# testbench.net
KiCad netlist of a schematic drawn in EAGLE
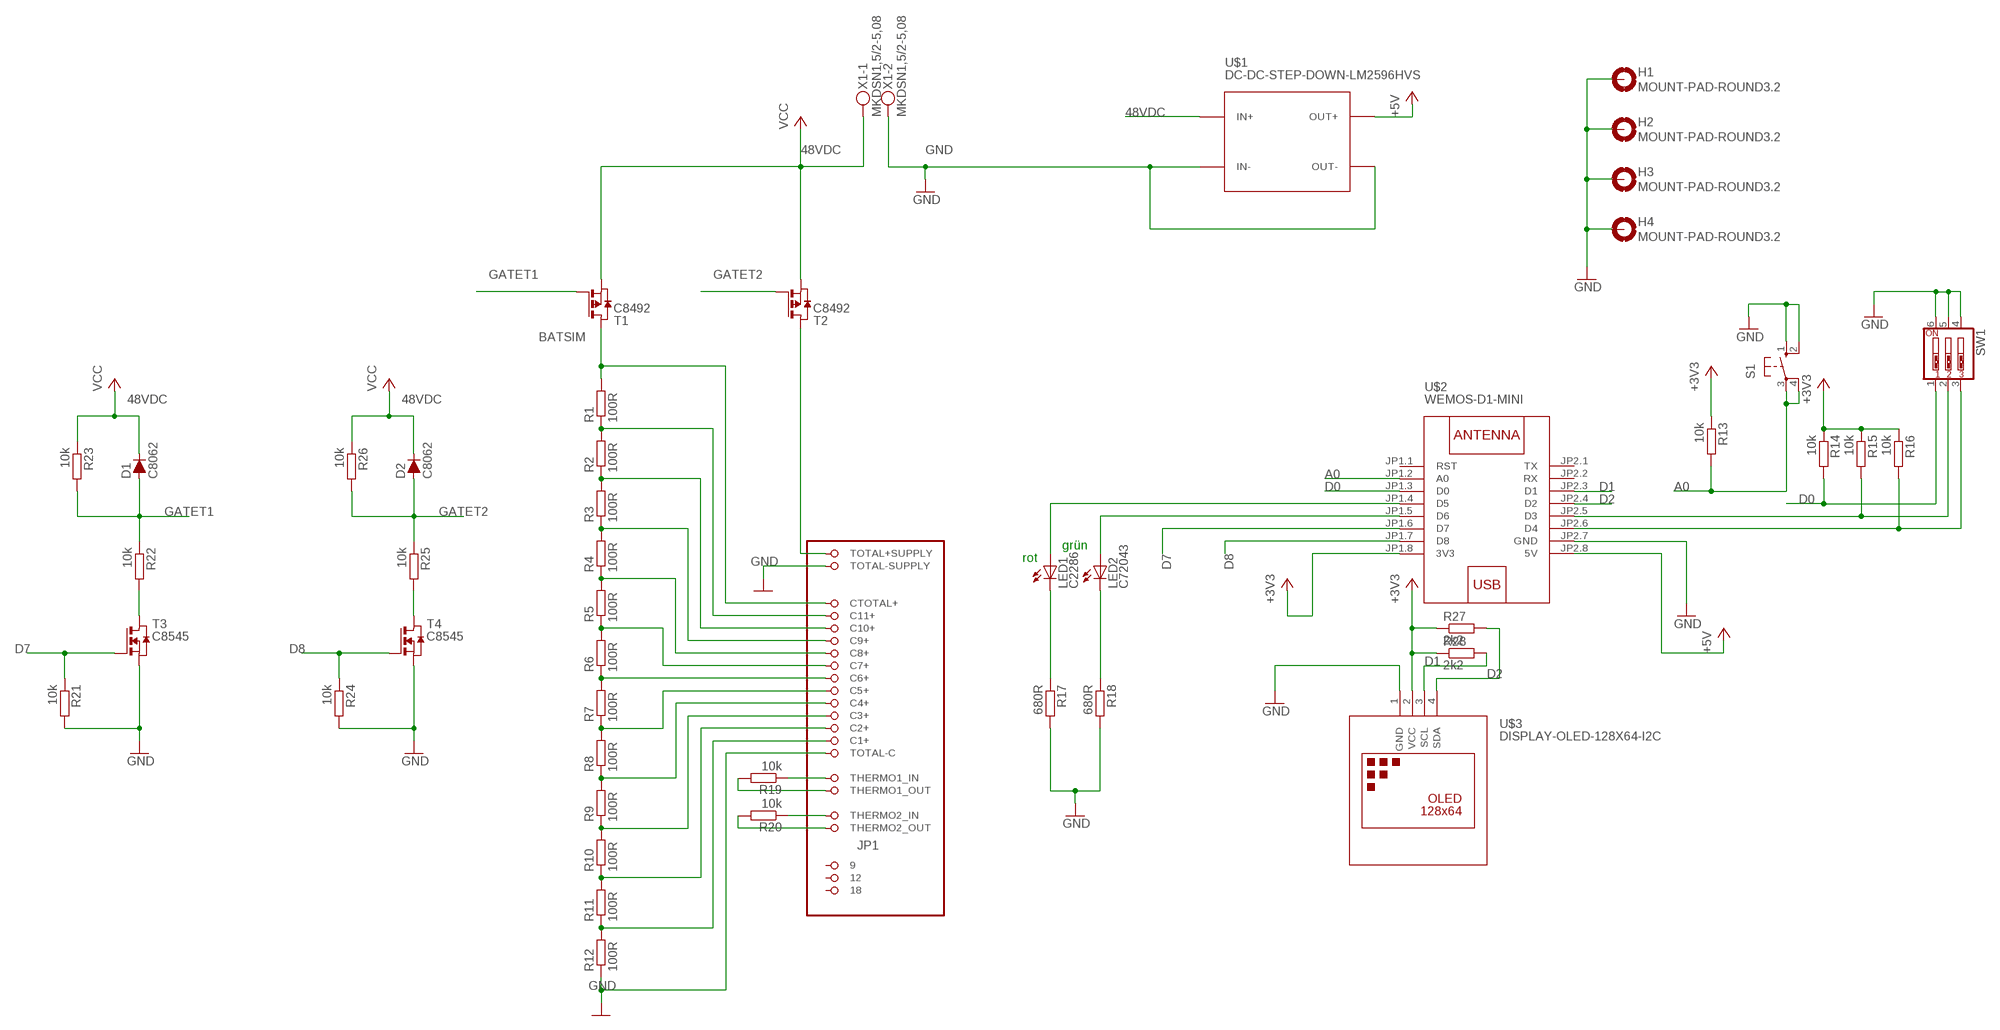
[diagram p0: schematic, sheet 1]

(export (version "E")
  (design (tool "Eeschema 10.0.6"))
  (components
    (comp (ref "D1")
      (value "C8062")
      (footprint "eagle-import:MELF-MLL34")
      (libsource (lib "eagle-import") (part "D-FILL-MLL-34"))
    )
    (comp (ref "D2")
      (value "C8062")
      (footprint "eagle-import:MELF-MLL34")
      (libsource (lib "eagle-import") (part "D-FILL-MLL-34"))
    )
    (comp (ref "H1")
      (value "MOUNT-PAD-ROUND3.2")
      (footprint "eagle-import:3,2-PAD")
      (libsource (lib "eagle-import") (part "MOUNT-PAD-ROUND3.2"))
    )
    (comp (ref "H2")
      (value "MOUNT-PAD-ROUND3.2")
      (footprint "eagle-import:3,2-PAD")
      (libsource (lib "eagle-import") (part "MOUNT-PAD-ROUND3.2"))
    )
    (comp (ref "H3")
      (value "MOUNT-PAD-ROUND3.2")
      (footprint "eagle-import:3,2-PAD")
      (libsource (lib "eagle-import") (part "MOUNT-PAD-ROUND3.2"))
    )
    (comp (ref "H4")
      (value "MOUNT-PAD-ROUND3.2")
      (footprint "eagle-import:3,2-PAD")
      (libsource (lib "eagle-import") (part "MOUNT-PAD-ROUND3.2"))
    )
    (comp (ref "JP1")
      (value "PINHD-2X11_MEB12S_MODULSEITE_SMD")
      (footprint "eagle-import:2X11_MEB12S_MODULSEITE_SMD")
      (libsource (lib "eagle-import") (part "PINHD-2X11_MEB12S_MODULSEITE_SMD"))
    )
    (comp (ref "LED1")
      (value "C2286")
      (footprint "eagle-import:CHIP-LED0603")
      (libsource (lib "eagle-import") (part "LEDCHIP-LED0603"))
    )
    (comp (ref "LED2")
      (value "C72043")
      (footprint "eagle-import:CHIP-LED0603")
      (libsource (lib "eagle-import") (part "LEDCHIP-LED0603"))
    )
    (comp (ref "R1")
      (value "100R")
      (footprint "eagle-import:R0805")
      (libsource (lib "eagle-import") (part "R-EU_R0805"))
    )
    (comp (ref "R2")
      (value "100R")
      (footprint "eagle-import:R0805")
      (libsource (lib "eagle-import") (part "R-EU_R0805"))
    )
    (comp (ref "R3")
      (value "100R")
      (footprint "eagle-import:R0805")
      (libsource (lib "eagle-import") (part "R-EU_R0805"))
    )
    (comp (ref "R4")
      (value "100R")
      (footprint "eagle-import:R0805")
      (libsource (lib "eagle-import") (part "R-EU_R0805"))
    )
    (comp (ref "R5")
      (value "100R")
      (footprint "eagle-import:R0805")
      (libsource (lib "eagle-import") (part "R-EU_R0805"))
    )
    (comp (ref "R6")
      (value "100R")
      (footprint "eagle-import:R0805")
      (libsource (lib "eagle-import") (part "R-EU_R0805"))
    )
    (comp (ref "R7")
      (value "100R")
      (footprint "eagle-import:R0805")
      (libsource (lib "eagle-import") (part "R-EU_R0805"))
    )
    (comp (ref "R8")
      (value "100R")
      (footprint "eagle-import:R0805")
      (libsource (lib "eagle-import") (part "R-EU_R0805"))
    )
    (comp (ref "R9")
      (value "100R")
      (footprint "eagle-import:R0805")
      (libsource (lib "eagle-import") (part "R-EU_R0805"))
    )
    (comp (ref "R10")
      (value "100R")
      (footprint "eagle-import:R0805")
      (libsource (lib "eagle-import") (part "R-EU_R0805"))
    )
    (comp (ref "R11")
      (value "100R")
      (footprint "eagle-import:R0805")
      (libsource (lib "eagle-import") (part "R-EU_R0805"))
    )
    (comp (ref "R12")
      (value "100R")
      (footprint "eagle-import:R0805")
      (libsource (lib "eagle-import") (part "R-EU_R0805"))
    )
    (comp (ref "R13")
      (value "10k")
      (footprint "eagle-import:R0805")
      (libsource (lib "eagle-import") (part "R-EU_R0805"))
    )
    (comp (ref "R14")
      (value "10k")
      (footprint "eagle-import:R0805")
      (libsource (lib "eagle-import") (part "R-EU_R0805"))
    )
    (comp (ref "R15")
      (value "10k")
      (footprint "eagle-import:R0805")
      (libsource (lib "eagle-import") (part "R-EU_R0805"))
    )
    (comp (ref "R16")
      (value "10k")
      (footprint "eagle-import:R0805")
      (libsource (lib "eagle-import") (part "R-EU_R0805"))
    )
    (comp (ref "R17")
      (value "680R")
      (footprint "eagle-import:R0805")
      (libsource (lib "eagle-import") (part "R-EU_R0805"))
    )
    (comp (ref "R18")
      (value "680R")
      (footprint "eagle-import:R0805")
      (libsource (lib "eagle-import") (part "R-EU_R0805"))
    )
    (comp (ref "R19")
      (value "10k")
      (footprint "eagle-import:R0805")
      (libsource (lib "eagle-import") (part "R-EU_R0805"))
    )
    (comp (ref "R20")
      (value "10k")
      (footprint "eagle-import:R0805")
      (libsource (lib "eagle-import") (part "R-EU_R0805"))
    )
    (comp (ref "R21")
      (value "10k")
      (footprint "eagle-import:R0805")
      (libsource (lib "eagle-import") (part "R-EU_R0805"))
    )
    (comp (ref "R22")
      (value "10k")
      (footprint "eagle-import:R0805")
      (libsource (lib "eagle-import") (part "R-EU_R0805"))
    )
    (comp (ref "R23")
      (value "10k")
      (footprint "eagle-import:R0805")
      (libsource (lib "eagle-import") (part "R-EU_R0805"))
    )
    (comp (ref "R24")
      (value "10k")
      (footprint "eagle-import:R0805")
      (libsource (lib "eagle-import") (part "R-EU_R0805"))
    )
    (comp (ref "R25")
      (value "10k")
      (footprint "eagle-import:R0805")
      (libsource (lib "eagle-import") (part "R-EU_R0805"))
    )
    (comp (ref "R26")
      (value "10k")
      (footprint "eagle-import:R0805")
      (libsource (lib "eagle-import") (part "R-EU_R0805"))
    )
    (comp (ref "R27")
      (value "2k2")
      (footprint "eagle-import:R0805")
      (libsource (lib "eagle-import") (part "R-EU_R0805"))
    )
    (comp (ref "R28")
      (value "2k2")
      (footprint "eagle-import:R0805")
      (libsource (lib "eagle-import") (part "R-EU_R0805"))
    )
    (comp (ref "S1")
      (value "10-XX")
      (footprint "eagle-import:B3F-10XX")
      (fields (field (name "MPN") "B3F-1000"))
      (libsource (lib "eagle-import") (part "10-XX"))
    )
    (comp (ref "SW1")
      (value "SW_DIP-3")
      (footprint "eagle-import:EDG-03")
      (libsource (lib "eagle-import") (part "SW_DIP-3"))
    )
    (comp (ref "T1")
      (value "C8492")
      (footprint "eagle-import:SOT-23")
      (libsource (lib "eagle-import") (part "PMOSSOT23"))
    )
    (comp (ref "T2")
      (value "C8492")
      (footprint "eagle-import:SOT-23")
      (libsource (lib "eagle-import") (part "PMOSSOT23"))
    )
    (comp (ref "T3")
      (value "C8545")
      (footprint "eagle-import:SOT-23")
      (libsource (lib "eagle-import") (part "NMOSSOT23"))
    )
    (comp (ref "T4")
      (value "C8545")
      (footprint "eagle-import:SOT-23")
      (libsource (lib "eagle-import") (part "NMOSSOT23"))
    )
    (comp (ref "U$1")
      (value "DC-DC-STEP-DOWN-LM2596HVS")
      (footprint "eagle-import:DC-DC-STEP-DOWN-LM2596HVS")
      (libsource (lib "eagle-import") (part "DC-DC-STEP-DOWN-LM2596HVS"))
    )
    (comp (ref "U$2")
      (value "WEMOS-D1-MINI")
      (footprint "eagle-import:WEMOS-D1-MINI")
      (libsource (lib "eagle-import") (part "WEMOS-D1-MINI"))
    )
    (comp (ref "U$3")
      (value "DISPLAY-OLED-128X64-I2C")
      (footprint "eagle-import:DISPLAY-OLED-128X64-I2C")
      (libsource (lib "eagle-import") (part "DISPLAY-OLED-128X64-I2C"))
    )
    (comp (ref "X1")
      (value "MKDSN1,5/2-5,08")
      (footprint "eagle-import:MKDSN1,5_2-5,08")
      (libsource (lib "eagle-import") (part "MKDSN1,5/2-5,08"))
    )
  )
  (nets
    (net (code "1") (name "+3V3") (class "Default")
      (node (ref "R13") (pin "1") (pinfunction "1_1") (pintype "passive"))
      (node (ref "R14") (pin "1") (pinfunction "1_1") (pintype "passive"))
      (node (ref "R15") (pin "1") (pinfunction "1_1") (pintype "passive"))
      (node (ref "R16") (pin "1") (pinfunction "1_1") (pintype "passive"))
      (node (ref "R27") (pin "1") (pinfunction "1_1") (pintype "passive"))
      (node (ref "R28") (pin "1") (pinfunction "1_1") (pintype "passive"))
      (node (ref "U$2") (pin "JP1.8") (pinfunction "3V3_JP1.8") (pintype "power_in"))
      (node (ref "U$3") (pin "2") (pinfunction "VCC_2") (pintype "power_in"))
    )
    (net (code "2") (name "+5V") (class "Default")
      (node (ref "U$1") (pin "OUT+") (pinfunction "OUT+_OUT+") (pintype "bidirectional"))
      (node (ref "U$2") (pin "JP2.8") (pinfunction "5V_JP2.8") (pintype "power_in"))
    )
    (net (code "3") (name "/A0") (class "Default")
      (node (ref "R13") (pin "2") (pinfunction "2_2") (pintype "passive"))
      (node (ref "S1") (pin "3") (pinfunction "P_3") (pintype "passive"))
      (node (ref "S1") (pin "4") (pinfunction "P1_4") (pintype "passive"))
      (node (ref "U$2") (pin "JP1.2") (pinfunction "A0_JP1.2") (pintype "bidirectional"))
    )
    (net (code "4") (name "/BATSIM") (class "Default")
      (node (ref "JP1") (pin "21") (pinfunction "CTOTAL+_21") (pintype "passive"))
      (node (ref "R1") (pin "2") (pinfunction "2_2") (pintype "passive"))
      (node (ref "T1") (pin "1") (pinfunction "D_1") (pintype "passive"))
    )
    (net (code "5") (name "/D0") (class "Default")
      (node (ref "R14") (pin "2") (pinfunction "2_2") (pintype "passive"))
      (node (ref "SW1") (pin "1") (pinfunction "1_1") (pintype "passive"))
      (node (ref "U$2") (pin "JP1.3") (pinfunction "D0_JP1.3") (pintype "bidirectional"))
    )
    (net (code "6") (name "/D1") (class "Default")
      (node (ref "R28") (pin "2") (pinfunction "2_2") (pintype "passive"))
      (node (ref "U$2") (pin "JP2.3") (pinfunction "D1_JP2.3") (pintype "bidirectional"))
      (node (ref "U$3") (pin "3") (pinfunction "SCL_3") (pintype "bidirectional"))
    )
    (net (code "7") (name "/D2") (class "Default")
      (node (ref "R27") (pin "2") (pinfunction "2_2") (pintype "passive"))
      (node (ref "U$2") (pin "JP2.4") (pinfunction "D2_JP2.4") (pintype "bidirectional"))
      (node (ref "U$3") (pin "4") (pinfunction "SDA_4") (pintype "bidirectional"))
    )
    (net (code "8") (name "/D7") (class "Default")
      (node (ref "R21") (pin "1") (pinfunction "1_1") (pintype "passive"))
      (node (ref "T3") (pin "3") (pinfunction "G_3") (pintype "passive"))
      (node (ref "U$2") (pin "JP1.6") (pinfunction "D7_JP1.6") (pintype "bidirectional"))
    )
    (net (code "9") (name "/D8") (class "Default")
      (node (ref "R24") (pin "1") (pinfunction "1_1") (pintype "passive"))
      (node (ref "T4") (pin "3") (pinfunction "G_3") (pintype "passive"))
      (node (ref "U$2") (pin "JP1.7") (pinfunction "D8_JP1.7") (pintype "bidirectional"))
    )
    (net (code "10") (name "/GATET1") (class "Default")
      (node (ref "D1") (pin "2") (pinfunction "A_2") (pintype "passive"))
      (node (ref "R22") (pin "1") (pinfunction "1_1") (pintype "passive"))
      (node (ref "R23") (pin "2") (pinfunction "2_2") (pintype "passive"))
      (node (ref "T1") (pin "3") (pinfunction "G_3") (pintype "passive"))
    )
    (net (code "11") (name "/GATET2") (class "Default")
      (node (ref "D2") (pin "2") (pinfunction "A_2") (pintype "passive"))
      (node (ref "R25") (pin "1") (pinfunction "1_1") (pintype "passive"))
      (node (ref "R26") (pin "2") (pinfunction "2_2") (pintype "passive"))
      (node (ref "T2") (pin "3") (pinfunction "G_3") (pintype "passive"))
    )
    (net (code "12") (name "GND") (class "Default")
      (node (ref "H1") (pin "B3,2") (pinfunction "MOUNT_B3,2") (pintype "passive"))
      (node (ref "H2") (pin "B3,2") (pinfunction "MOUNT_B3,2") (pintype "passive"))
      (node (ref "H3") (pin "B3,2") (pinfunction "MOUNT_B3,2") (pintype "passive"))
      (node (ref "H4") (pin "B3,2") (pinfunction "MOUNT_B3,2") (pintype "passive"))
      (node (ref "JP1") (pin "7") (pinfunction "TOTAL-SUPPLY_7") (pintype "passive"))
      (node (ref "JP1") (pin "9") (pinfunction "TOTAL-C_9") (pintype "passive"))
      (node (ref "R12") (pin "1") (pinfunction "1_1") (pintype "passive"))
      (node (ref "R17") (pin "2") (pinfunction "2_2") (pintype "passive"))
      (node (ref "R18") (pin "2") (pinfunction "2_2") (pintype "passive"))
      (node (ref "R21") (pin "2") (pinfunction "2_2") (pintype "passive"))
      (node (ref "R24") (pin "2") (pinfunction "2_2") (pintype "passive"))
      (node (ref "S1") (pin "1") (pinfunction "S_1") (pintype "passive"))
      (node (ref "S1") (pin "2") (pinfunction "S1_2") (pintype "passive"))
      (node (ref "SW1") (pin "4") (pinfunction "4_4") (pintype "passive"))
      (node (ref "SW1") (pin "5") (pinfunction "5_5") (pintype "passive"))
      (node (ref "SW1") (pin "6") (pinfunction "6_6") (pintype "passive"))
      (node (ref "T3") (pin "2") (pinfunction "S_2") (pintype "passive"))
      (node (ref "T4") (pin "2") (pinfunction "S_2") (pintype "passive"))
      (node (ref "U$1") (pin "IN-") (pinfunction "IN-_IN-") (pintype "bidirectional"))
      (node (ref "U$1") (pin "OUT-") (pinfunction "OUT-_OUT-") (pintype "bidirectional"))
      (node (ref "U$2") (pin "JP2.7") (pinfunction "GND_JP2.7") (pintype "power_in"))
      (node (ref "U$3") (pin "1") (pinfunction "GND_1") (pintype "power_in"))
      (node (ref "X1") (pin "2") (pinfunction "KL_2") (pintype "passive"))
    )
    (net (code "13") (name "Net-(JP1-C1+)") (class "Default")
      (node (ref "JP1") (pin "10") (pinfunction "C1+_10") (pintype "passive"))
      (node (ref "R11") (pin "1") (pinfunction "1_1") (pintype "passive"))
      (node (ref "R12") (pin "2") (pinfunction "2_2") (pintype "passive"))
    )
    (net (code "14") (name "Net-(JP1-C2+)") (class "Default")
      (node (ref "JP1") (pin "11") (pinfunction "C2+_11") (pintype "passive"))
      (node (ref "R10") (pin "1") (pinfunction "1_1") (pintype "passive"))
      (node (ref "R11") (pin "2") (pinfunction "2_2") (pintype "passive"))
    )
    (net (code "15") (name "Net-(JP1-C3+)") (class "Default")
      (node (ref "JP1") (pin "12") (pinfunction "C3+_12") (pintype "passive"))
      (node (ref "R10") (pin "2") (pinfunction "2_2") (pintype "passive"))
      (node (ref "R9") (pin "1") (pinfunction "1_1") (pintype "passive"))
    )
    (net (code "16") (name "Net-(JP1-C4+)") (class "Default")
      (node (ref "JP1") (pin "13") (pinfunction "C4+_13") (pintype "passive"))
      (node (ref "R8") (pin "1") (pinfunction "1_1") (pintype "passive"))
      (node (ref "R9") (pin "2") (pinfunction "2_2") (pintype "passive"))
    )
    (net (code "17") (name "Net-(JP1-C5+)") (class "Default")
      (node (ref "JP1") (pin "14") (pinfunction "C5+_14") (pintype "passive"))
      (node (ref "R7") (pin "1") (pinfunction "1_1") (pintype "passive"))
      (node (ref "R8") (pin "2") (pinfunction "2_2") (pintype "passive"))
    )
    (net (code "18") (name "Net-(JP1-C6+)") (class "Default")
      (node (ref "JP1") (pin "15") (pinfunction "C6+_15") (pintype "passive"))
      (node (ref "R6") (pin "1") (pinfunction "1_1") (pintype "passive"))
      (node (ref "R7") (pin "2") (pinfunction "2_2") (pintype "passive"))
    )
    (net (code "19") (name "Net-(JP1-C7+)") (class "Default")
      (node (ref "JP1") (pin "16") (pinfunction "C7+_16") (pintype "passive"))
      (node (ref "R5") (pin "1") (pinfunction "1_1") (pintype "passive"))
      (node (ref "R6") (pin "2") (pinfunction "2_2") (pintype "passive"))
    )
    (net (code "20") (name "Net-(JP1-C8+)") (class "Default")
      (node (ref "JP1") (pin "17") (pinfunction "C8+_17") (pintype "passive"))
      (node (ref "R4") (pin "1") (pinfunction "1_1") (pintype "passive"))
      (node (ref "R5") (pin "2") (pinfunction "2_2") (pintype "passive"))
    )
    (net (code "21") (name "Net-(JP1-C9+)") (class "Default")
      (node (ref "JP1") (pin "18") (pinfunction "C9+_18") (pintype "passive"))
      (node (ref "R3") (pin "1") (pinfunction "1_1") (pintype "passive"))
      (node (ref "R4") (pin "2") (pinfunction "2_2") (pintype "passive"))
    )
    (net (code "22") (name "Net-(JP1-C10+)") (class "Default")
      (node (ref "JP1") (pin "19") (pinfunction "C10+_19") (pintype "passive"))
      (node (ref "R2") (pin "1") (pinfunction "1_1") (pintype "passive"))
      (node (ref "R3") (pin "2") (pinfunction "2_2") (pintype "passive"))
    )
    (net (code "23") (name "Net-(JP1-C11+)") (class "Default")
      (node (ref "JP1") (pin "20") (pinfunction "C11+_20") (pintype "passive"))
      (node (ref "R1") (pin "1") (pinfunction "1_1") (pintype "passive"))
      (node (ref "R2") (pin "2") (pinfunction "2_2") (pintype "passive"))
    )
    (net (code "24") (name "Net-(JP1-THERMO1_IN)") (class "Default")
      (node (ref "JP1") (pin "1") (pinfunction "THERMO1_IN_1") (pintype "passive"))
      (node (ref "R19") (pin "1") (pinfunction "1_1") (pintype "passive"))
    )
    (net (code "25") (name "Net-(JP1-THERMO1_OUT)") (class "Default")
      (node (ref "JP1") (pin "3") (pinfunction "THERMO1_OUT_3") (pintype "passive"))
      (node (ref "R19") (pin "2") (pinfunction "2_2") (pintype "passive"))
    )
    (net (code "26") (name "Net-(JP1-THERMO2_IN)") (class "Default")
      (node (ref "JP1") (pin "2") (pinfunction "THERMO2_IN_2") (pintype "passive"))
      (node (ref "R20") (pin "1") (pinfunction "1_1") (pintype "passive"))
    )
    (net (code "27") (name "Net-(JP1-THERMO2_OUT)") (class "Default")
      (node (ref "JP1") (pin "4") (pinfunction "THERMO2_OUT_4") (pintype "passive"))
      (node (ref "R20") (pin "2") (pinfunction "2_2") (pintype "passive"))
    )
    (net (code "28") (name "Net-(JP1-TOTAL+SUPPLY)") (class "Default")
      (node (ref "JP1") (pin "22") (pinfunction "TOTAL+SUPPLY_22") (pintype "passive"))
      (node (ref "T2") (pin "1") (pinfunction "D_1") (pintype "passive"))
    )
    (net (code "29") (name "Net-(LED1-PadC)") (class "Default")
      (node (ref "LED1") (pin "C") (pinfunction "C_C") (pintype "passive"))
      (node (ref "R17") (pin "1") (pinfunction "1_1") (pintype "passive"))
    )
    (net (code "30") (name "Net-(LED2-PadC)") (class "Default")
      (node (ref "LED2") (pin "C") (pinfunction "C_C") (pintype "passive"))
      (node (ref "R18") (pin "1") (pinfunction "1_1") (pintype "passive"))
    )
    (net (code "31") (name "Net-(T3-D)") (class "Default")
      (node (ref "R22") (pin "2") (pinfunction "2_2") (pintype "passive"))
      (node (ref "T3") (pin "1") (pinfunction "D_1") (pintype "passive"))
    )
    (net (code "32") (name "Net-(T4-D)") (class "Default")
      (node (ref "R25") (pin "2") (pinfunction "2_2") (pintype "passive"))
      (node (ref "T4") (pin "1") (pinfunction "D_1") (pintype "passive"))
    )
    (net (code "33") (name "Net-(U$2-D3)") (class "Default")
      (node (ref "R15") (pin "2") (pinfunction "2_2") (pintype "passive"))
      (node (ref "SW1") (pin "2") (pinfunction "2_2") (pintype "passive"))
      (node (ref "U$2") (pin "JP2.5") (pinfunction "D3_JP2.5") (pintype "bidirectional"))
    )
    (net (code "34") (name "Net-(U$2-D4)") (class "Default")
      (node (ref "R16") (pin "2") (pinfunction "2_2") (pintype "passive"))
      (node (ref "SW1") (pin "3") (pinfunction "3_3") (pintype "passive"))
      (node (ref "U$2") (pin "JP2.6") (pinfunction "D4_JP2.6") (pintype "bidirectional"))
    )
    (net (code "35") (name "Net-(U$2-D5)") (class "Default")
      (node (ref "LED1") (pin "A") (pinfunction "A_A") (pintype "passive"))
      (node (ref "U$2") (pin "JP1.4") (pinfunction "D5_JP1.4") (pintype "bidirectional"))
    )
    (net (code "36") (name "Net-(U$2-D6)") (class "Default")
      (node (ref "LED2") (pin "A") (pinfunction "A_A") (pintype "passive"))
      (node (ref "U$2") (pin "JP1.5") (pinfunction "D6_JP1.5") (pintype "bidirectional"))
    )
    (net (code "37") (name "VCC") (class "Default")
      (node (ref "D1") (pin "1") (pinfunction "C_1") (pintype "passive"))
      (node (ref "D2") (pin "1") (pinfunction "C_1") (pintype "passive"))
      (node (ref "R23") (pin "1") (pinfunction "1_1") (pintype "passive"))
      (node (ref "R26") (pin "1") (pinfunction "1_1") (pintype "passive"))
      (node (ref "T1") (pin "2") (pinfunction "S_2") (pintype "passive"))
      (node (ref "T2") (pin "2") (pinfunction "S_2") (pintype "passive"))
      (node (ref "U$1") (pin "IN+") (pinfunction "IN+_IN+") (pintype "bidirectional"))
      (node (ref "X1") (pin "1") (pinfunction "KL_1") (pintype "passive"))
    )
    (net (code "38") (name "unconnected-(JP1-9-Pad5)") (class "Default")
      (node (ref "JP1") (pin "5") (pinfunction "9_5") (pintype "passive"))
    )
    (net (code "39") (name "unconnected-(JP1-12-Pad6)") (class "Default")
      (node (ref "JP1") (pin "6") (pinfunction "12_6") (pintype "passive"))
    )
    (net (code "40") (name "unconnected-(JP1-18-Pad8)") (class "Default")
      (node (ref "JP1") (pin "8") (pinfunction "18_8") (pintype "passive"))
    )
    (net (code "41") (name "unconnected-(U$2-RST-PadJP1.1)") (class "Default")
      (node (ref "U$2") (pin "JP1.1") (pinfunction "RST_JP1.1") (pintype "bidirectional"))
    )
    (net (code "42") (name "unconnected-(U$2-RX-PadJP2.2)") (class "Default")
      (node (ref "U$2") (pin "JP2.2") (pinfunction "RX_JP2.2") (pintype "bidirectional"))
    )
    (net (code "43") (name "unconnected-(U$2-TX-PadJP2.1)") (class "Default")
      (node (ref "U$2") (pin "JP2.1") (pinfunction "TX_JP2.1") (pintype "bidirectional"))
    )
  )
)
